# ARK.net
KiCad netlist of a schematic drawn in EAGLE
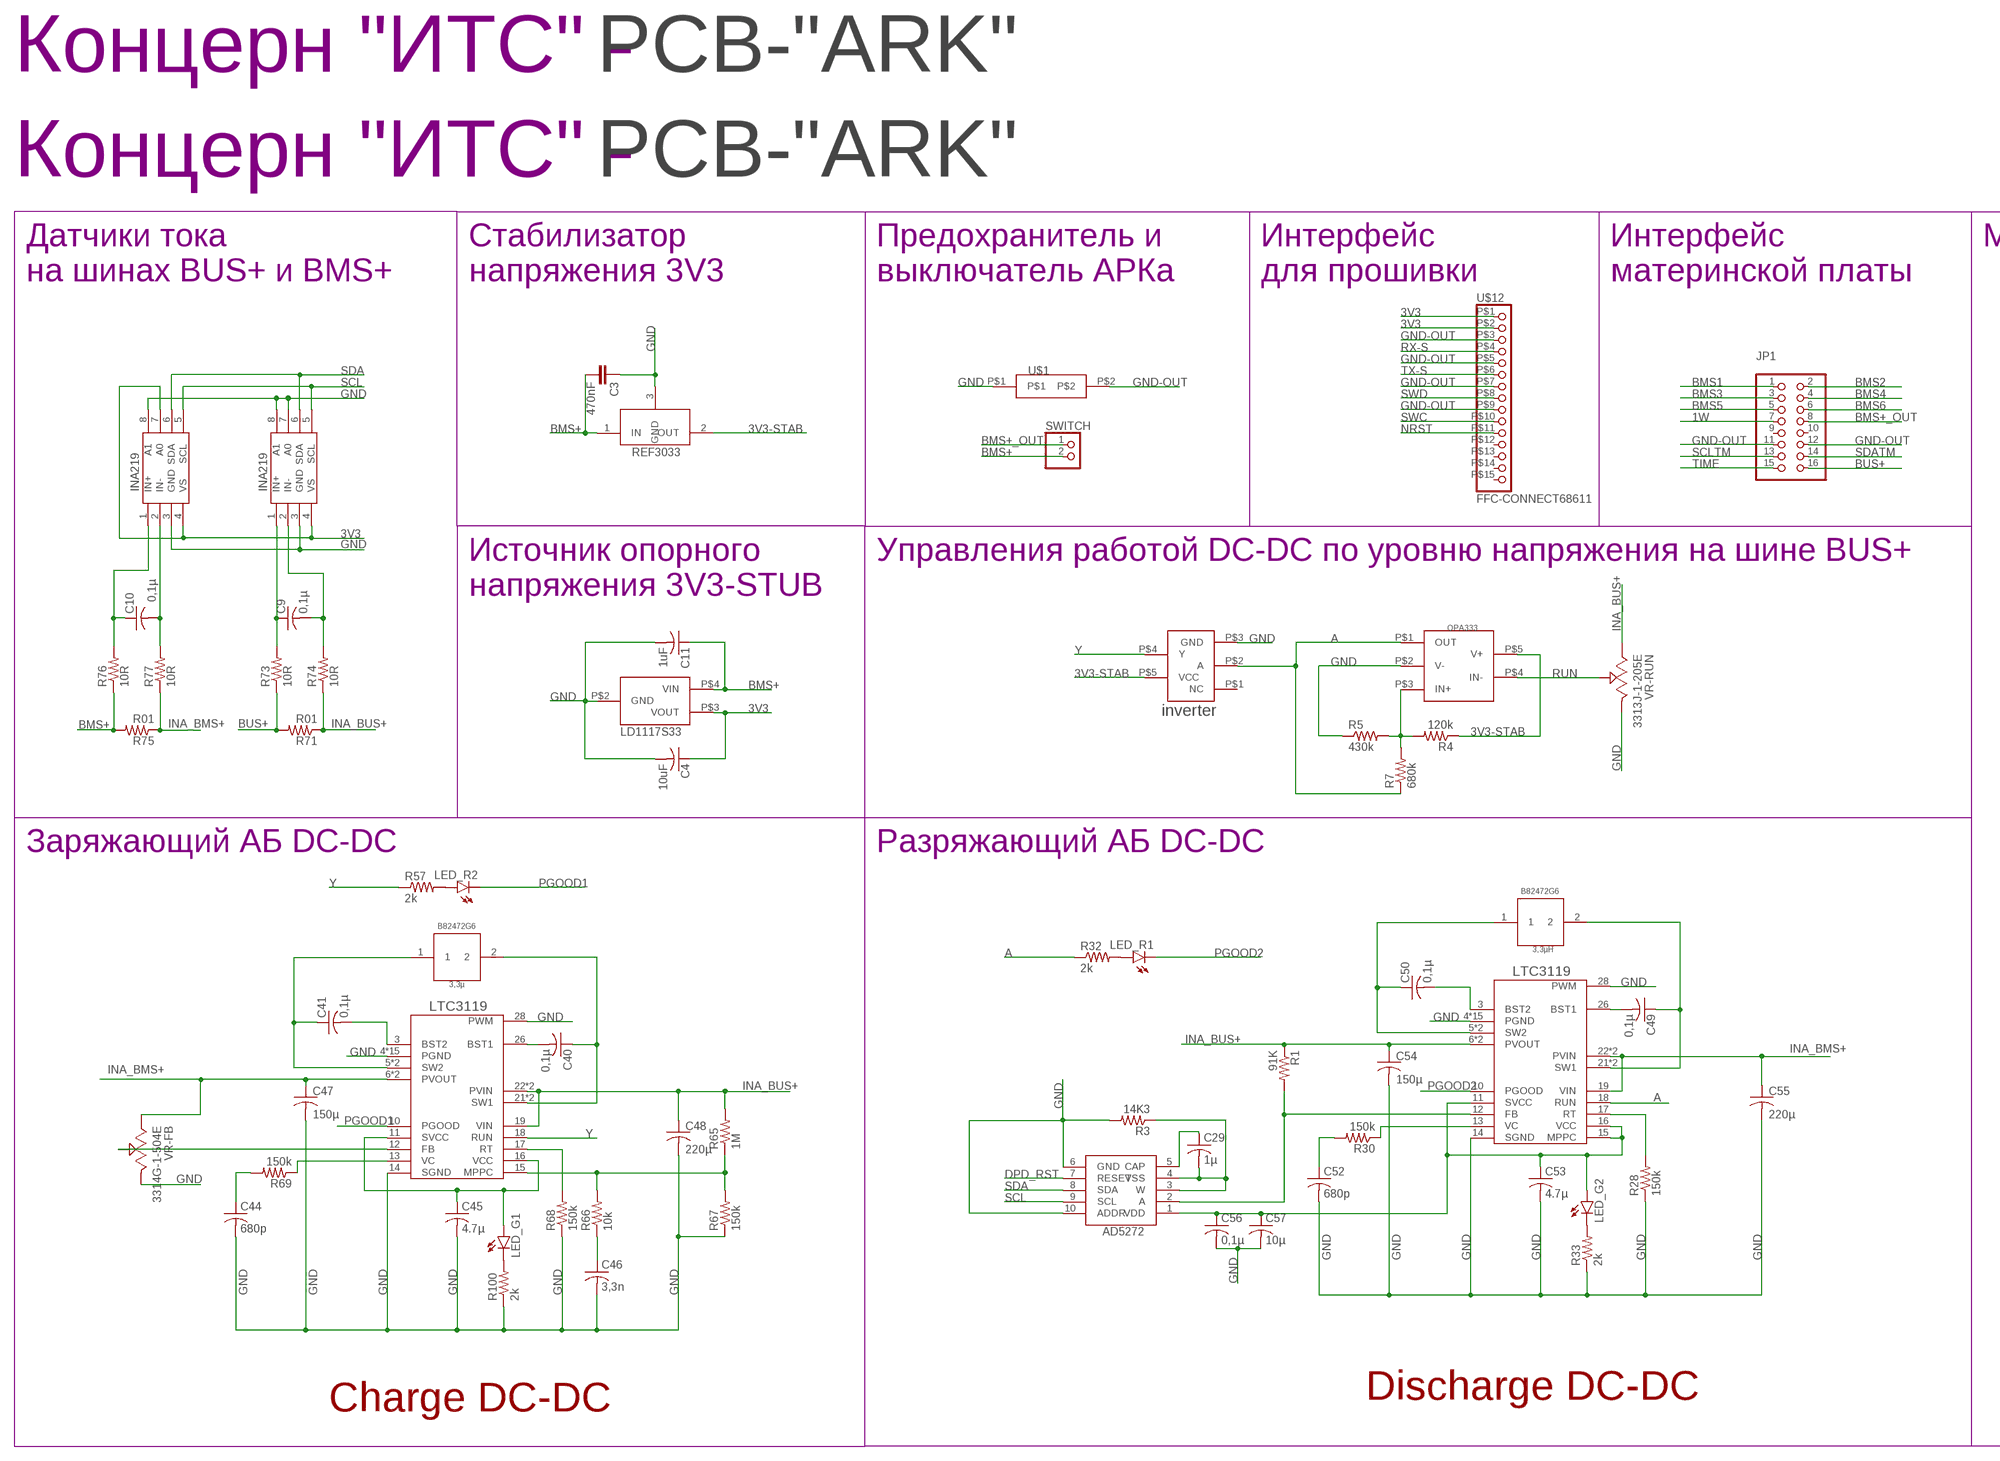
[diagram p0: schematic, sheet 1, part 1 of 2]
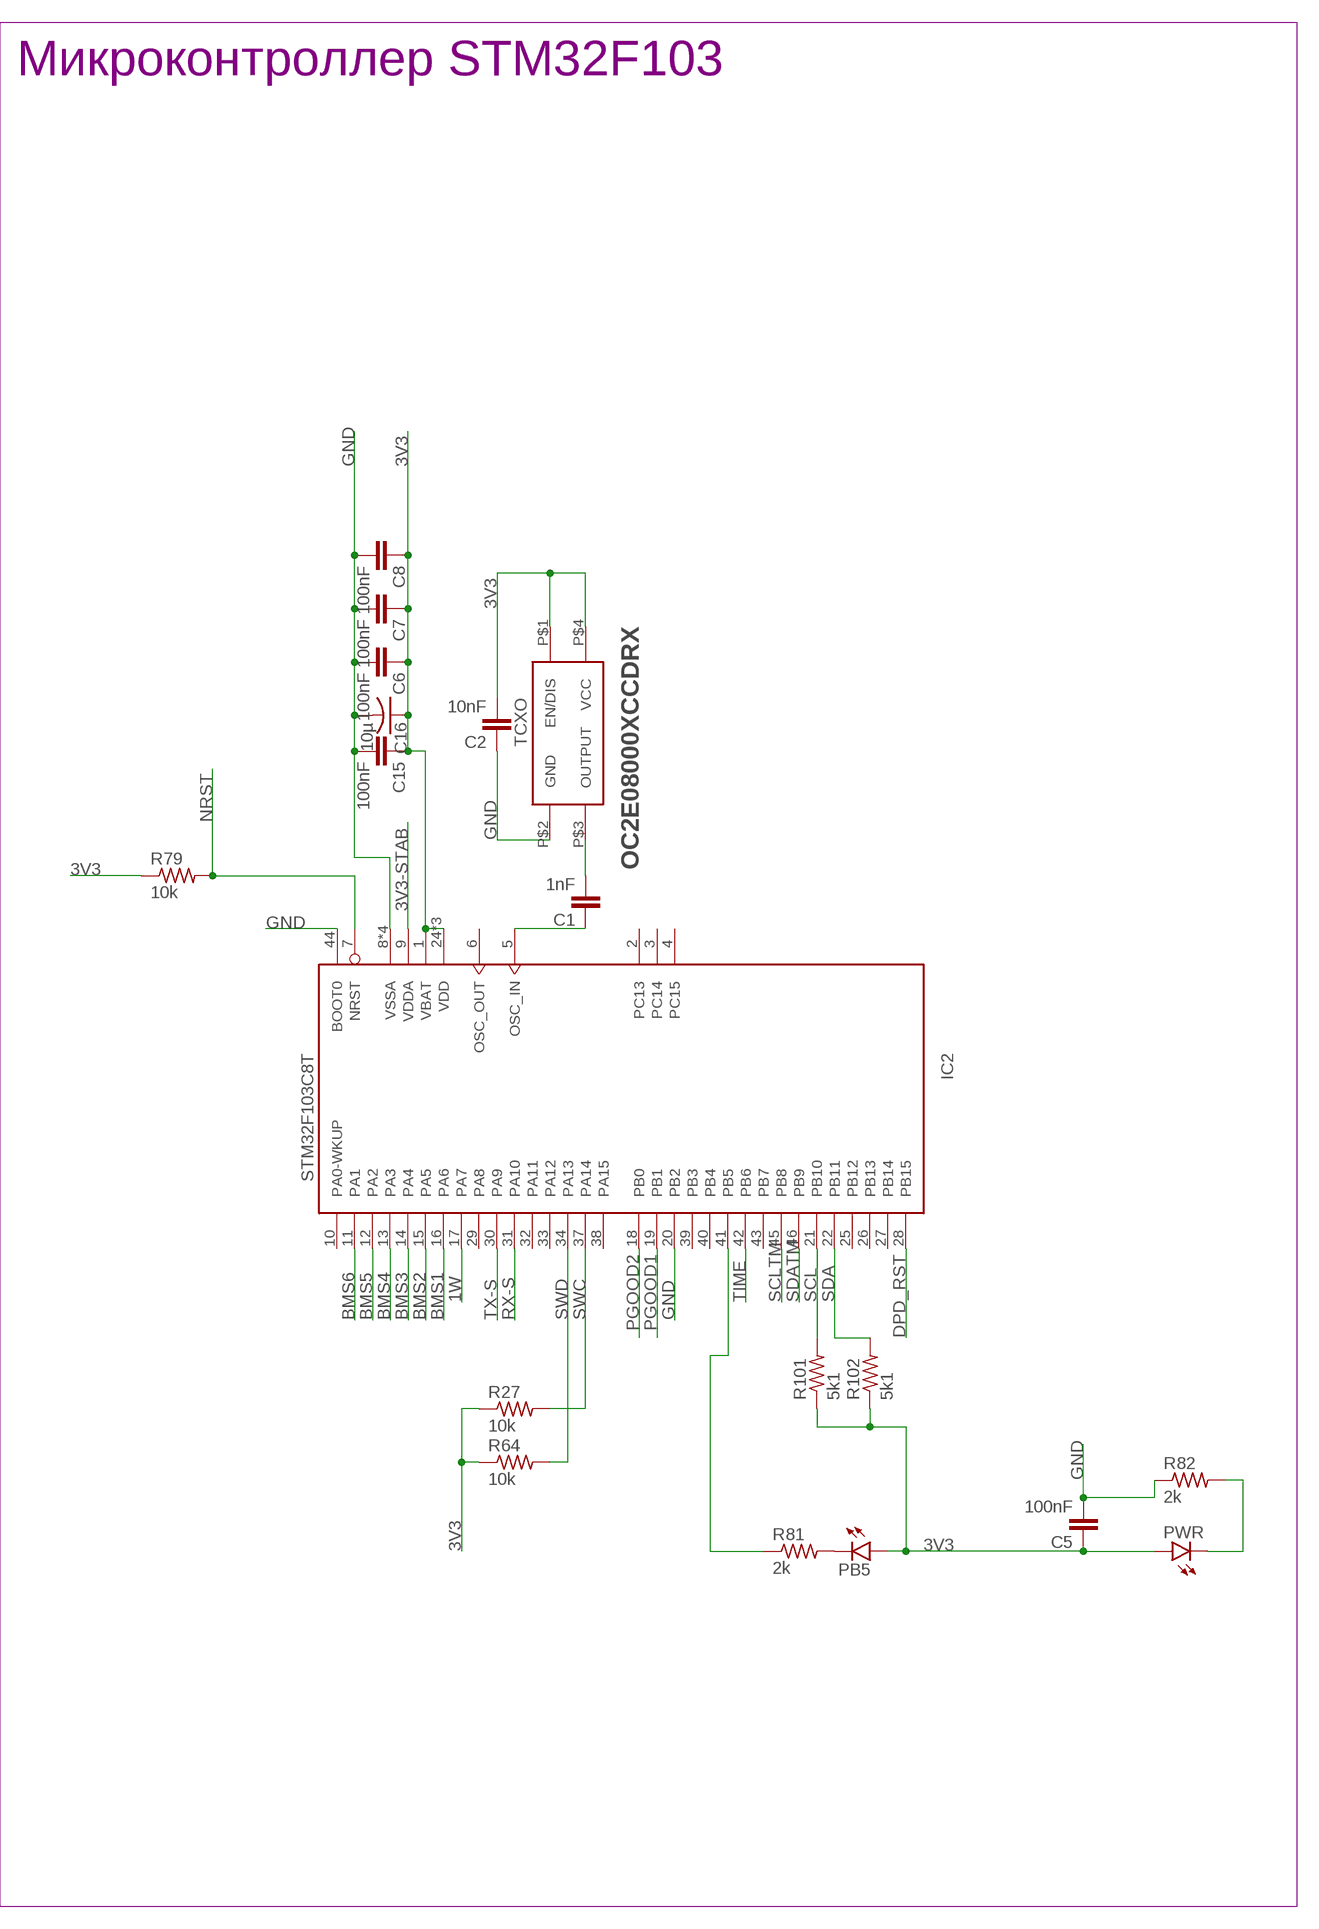
[diagram p1: schematic, sheet 1, part 2 of 2]

(export (version "E")
  (design (tool "Eeschema 10.0.6"))
  (components
    (comp (ref "3,3µH")
      (value "3,3µ")
      (footprint "eagle-import:B82472G6")
      (libsource (lib "eagle-import") (part "B82472G6"))
    )
    (comp (ref "3,3µH1")
      (value "3,3µH")
      (footprint "eagle-import:B82472G6")
      (libsource (lib "eagle-import") (part "B82472G6"))
    )
    (comp (ref "AD5272#2")
      (value "AD5272")
      (footprint "eagle-import:MSOP10")
      (libsource (lib "eagle-import") (part "AD5272"))
    )
    (comp (ref "C1")
      (value "1nF")
      (footprint "eagle-import:C0603")
      (libsource (lib "eagle-import") (part "C-EUC0603"))
    )
    (comp (ref "C2")
      (value "10nF")
      (footprint "eagle-import:C0603")
      (libsource (lib "eagle-import") (part "C-EUC0603"))
    )
    (comp (ref "C3")
      (value "470nF")
      (footprint "eagle-import:C0603")
      (libsource (lib "eagle-import") (part "C-EUC0603"))
    )
    (comp (ref "C4")
      (value "10uF")
      (footprint "eagle-import:ECAP-SMD-D4")
      (libsource (lib "eagle-import") (part "ECAP1UF"))
    )
    (comp (ref "C5")
      (value "100nF")
      (footprint "eagle-import:C0603")
      (libsource (lib "eagle-import") (part "C-EUC0603"))
    )
    (comp (ref "C6")
      (value "100nF")
      (footprint "eagle-import:C0603")
      (libsource (lib "eagle-import") (part "C-EUC0603"))
    )
    (comp (ref "C7")
      (value "100nF")
      (footprint "eagle-import:C0603")
      (libsource (lib "eagle-import") (part "C-EUC0603"))
    )
    (comp (ref "C8")
      (value "100nF")
      (footprint "eagle-import:C0603")
      (libsource (lib "eagle-import") (part "C-EUC0603"))
    )
    (comp (ref "C9")
      (value "0,1µ")
      (footprint "eagle-import:C0603")
      (libsource (lib "eagle-import") (part "C-USC0603"))
    )
    (comp (ref "C10")
      (value "0,1µ")
      (footprint "eagle-import:C0603")
      (libsource (lib "eagle-import") (part "C-USC0603"))
    )
    (comp (ref "C11")
      (value "1uF")
      (footprint "eagle-import:ECAP-SMD-D4")
      (libsource (lib "eagle-import") (part "ECAP1UF"))
    )
    (comp (ref "C15")
      (value "100nF")
      (footprint "eagle-import:C0603")
      (libsource (lib "eagle-import") (part "C-EUC0603"))
    )
    (comp (ref "C16")
      (value "10µ")
      (footprint "eagle-import:C1206")
      (libsource (lib "eagle-import") (part "C-USC1206"))
    )
    (comp (ref "C29")
      (value "1µ")
      (footprint "eagle-import:C0603")
      (libsource (lib "eagle-import") (part "C-USC0603"))
    )
    (comp (ref "C40")
      (value "0,1µ")
      (footprint "eagle-import:C0603")
      (libsource (lib "eagle-import") (part "C-USC0603"))
    )
    (comp (ref "C41")
      (value "0,1µ")
      (footprint "eagle-import:C0603")
      (libsource (lib "eagle-import") (part "C-USC0603"))
    )
    (comp (ref "C44")
      (value "680p")
      (footprint "eagle-import:C0603")
      (libsource (lib "eagle-import") (part "C-USC0603"))
    )
    (comp (ref "C45")
      (value "4.7µ")
      (footprint "eagle-import:C1206")
      (libsource (lib "eagle-import") (part "C-USC1206"))
    )
    (comp (ref "C46")
      (value "3,3n")
      (footprint "eagle-import:C0603")
      (libsource (lib "eagle-import") (part "C-USC0603"))
    )
    (comp (ref "C47")
      (value "150µ")
      (footprint "eagle-import:ECAP150-CMD")
      (libsource (lib "eagle-import") (part "ECAPECAP150"))
    )
    (comp (ref "C48")
      (value "220µ")
      (footprint "eagle-import:ECAP220-CMD")
      (libsource (lib "eagle-import") (part "ECAPECAP220"))
    )
    (comp (ref "C49")
      (value "0,1µ")
      (footprint "eagle-import:C0603")
      (libsource (lib "eagle-import") (part "C-USC0603"))
    )
    (comp (ref "C50")
      (value "0,1µ")
      (footprint "eagle-import:C0603")
      (libsource (lib "eagle-import") (part "C-USC0603"))
    )
    (comp (ref "C52")
      (value "680p")
      (footprint "eagle-import:C0603")
      (libsource (lib "eagle-import") (part "C-USC0603"))
    )
    (comp (ref "C53")
      (value "4.7µ")
      (footprint "eagle-import:C1206")
      (libsource (lib "eagle-import") (part "C-USC1206"))
    )
    (comp (ref "C54")
      (value "150µ")
      (footprint "eagle-import:ECAP150-CMD")
      (libsource (lib "eagle-import") (part "ECAPECAP150"))
    )
    (comp (ref "C55")
      (value "220µ")
      (footprint "eagle-import:ECAP220-CMD")
      (libsource (lib "eagle-import") (part "ECAPECAP220"))
    )
    (comp (ref "C56")
      (value "0,1µ")
      (footprint "eagle-import:C0603")
      (libsource (lib "eagle-import") (part "C-USC0603"))
    )
    (comp (ref "C57")
      (value "10µ")
      (footprint "eagle-import:C1206")
      (libsource (lib "eagle-import") (part "C-USC1206"))
    )
    (comp (ref "IC2")
      (value "STM32F103C8T")
      (footprint "eagle-import:LQFP48")
      (libsource (lib "eagle-import") (part "STM32F103CT8"))
    )
    (comp (ref "INA219#1")
      (value "INA219AID")
      (footprint "eagle-import:SOT23-8")
      (libsource (lib "eagle-import") (part "INA219AID"))
    )
    (comp (ref "INA219#2")
      (value "INA219AID")
      (footprint "eagle-import:SOT23-8")
      (libsource (lib "eagle-import") (part "INA219AID"))
    )
    (comp (ref "INVERT")
      (value "INVERTER.")
      (footprint "eagle-import:SC70")
      (libsource (lib "eagle-import") (part "INVERTER."))
    )
    (comp (ref "JP1")
      (value "PINHD-2X8")
      (footprint "eagle-import:2X08")
      (libsource (lib "eagle-import") (part "PINHD-2X8"))
    )
    (comp (ref "LD1117S33")
      (value "LD1117S33")
      (footprint "eagle-import:SOT223")
      (libsource (lib "eagle-import") (part "LD1117S33"))
    )
    (comp (ref "LED_G1")
      (value "LEDCHIPLED_0603")
      (footprint "eagle-import:CHIPLED_0603")
      (libsource (lib "eagle-import") (part "LEDCHIPLED_0603"))
    )
    (comp (ref "LED_G2")
      (value "LEDCHIPLED_0603")
      (footprint "eagle-import:CHIPLED_0603")
      (libsource (lib "eagle-import") (part "LEDCHIPLED_0603"))
    )
    (comp (ref "LED_R1")
      (value "LEDCHIPLED_0603")
      (footprint "eagle-import:CHIPLED_0603")
      (libsource (lib "eagle-import") (part "LEDCHIPLED_0603"))
    )
    (comp (ref "LED_R2")
      (value "LEDCHIPLED_0603")
      (footprint "eagle-import:CHIPLED_0603")
      (libsource (lib "eagle-import") (part "LEDCHIPLED_0603"))
    )
    (comp (ref "OPA")
      (value "OPA333")
      (footprint "eagle-import:SOT23-5")
      (libsource (lib "eagle-import") (part "OPA333"))
    )
    (comp (ref "PB5")
      (value "LEDCHIPLED_0603")
      (footprint "eagle-import:CHIPLED_0603")
      (libsource (lib "eagle-import") (part "LEDCHIPLED_0603"))
    )
    (comp (ref "PWR")
      (value "LEDCHIPLED_0603")
      (footprint "eagle-import:CHIPLED_0603")
      (libsource (lib "eagle-import") (part "LEDCHIPLED_0603"))
    )
    (comp (ref "R1")
      (value "91K")
      (footprint "eagle-import:R0603")
      (libsource (lib "eagle-import") (part "resistor_R-US_R0603"))
    )
    (comp (ref "R3")
      (value "14K3")
      (footprint "eagle-import:R0603")
      (libsource (lib "eagle-import") (part "resistor_R-US_R0603"))
    )
    (comp (ref "R4")
      (value "120k")
      (footprint "eagle-import:R0603")
      (libsource (lib "eagle-import") (part "resistor_R-US_R0603"))
    )
    (comp (ref "R5")
      (value "430k")
      (footprint "eagle-import:R0603")
      (libsource (lib "eagle-import") (part "resistor_R-US_R0603"))
    )
    (comp (ref "R7")
      (value "680k")
      (footprint "eagle-import:R0603")
      (libsource (lib "eagle-import") (part "resistor_R-US_R0603"))
    )
    (comp (ref "R27")
      (value "10k")
      (footprint "eagle-import:R0603")
      (libsource (lib "eagle-import") (part "resistor_R-US_R0603"))
    )
    (comp (ref "R28")
      (value "150k")
      (footprint "eagle-import:R0603")
      (libsource (lib "eagle-import") (part "resistor_R-US_R0603"))
    )
    (comp (ref "R30")
      (value "150k")
      (footprint "eagle-import:R0603")
      (libsource (lib "eagle-import") (part "resistor_R-US_R0603"))
    )
    (comp (ref "R32")
      (value "2k")
      (footprint "eagle-import:R0603")
      (libsource (lib "eagle-import") (part "resistor_R-US_R0603"))
    )
    (comp (ref "R33")
      (value "2k")
      (footprint "eagle-import:R0603")
      (libsource (lib "eagle-import") (part "resistor_R-US_R0603"))
    )
    (comp (ref "R57")
      (value "2k")
      (footprint "eagle-import:R0603")
      (libsource (lib "eagle-import") (part "resistor_R-US_R0603"))
    )
    (comp (ref "R64")
      (value "10k")
      (footprint "eagle-import:R0603")
      (libsource (lib "eagle-import") (part "resistor_R-US_R0603"))
    )
    (comp (ref "R65")
      (value "1M")
      (footprint "eagle-import:R0603")
      (libsource (lib "eagle-import") (part "resistor_R-US_R0603"))
    )
    (comp (ref "R66")
      (value "10k")
      (footprint "eagle-import:R0603")
      (libsource (lib "eagle-import") (part "resistor_R-US_R0603"))
    )
    (comp (ref "R67")
      (value "150k")
      (footprint "eagle-import:R0603")
      (libsource (lib "eagle-import") (part "resistor_R-US_R0603"))
    )
    (comp (ref "R68")
      (value "150k")
      (footprint "eagle-import:R0603")
      (libsource (lib "eagle-import") (part "resistor_R-US_R0603"))
    )
    (comp (ref "R69")
      (value "150k")
      (footprint "eagle-import:R0603")
      (libsource (lib "eagle-import") (part "resistor_R-US_R0603"))
    )
    (comp (ref "R71")
      (value "R01")
      (footprint "eagle-import:R2512")
      (libsource (lib "eagle-import") (part "R-US_R2512"))
    )
    (comp (ref "R73")
      (value "10R")
      (footprint "eagle-import:R0603")
      (libsource (lib "eagle-import") (part "resistor_R-US_R0603"))
    )
    (comp (ref "R74")
      (value "10R")
      (footprint "eagle-import:R0603")
      (libsource (lib "eagle-import") (part "resistor_R-US_R0603"))
    )
    (comp (ref "R75")
      (value "R01")
      (footprint "eagle-import:R2512")
      (libsource (lib "eagle-import") (part "R-US_R2512"))
    )
    (comp (ref "R76")
      (value "10R")
      (footprint "eagle-import:R0603")
      (libsource (lib "eagle-import") (part "resistor_R-US_R0603"))
    )
    (comp (ref "R77")
      (value "10R")
      (footprint "eagle-import:R0603")
      (libsource (lib "eagle-import") (part "resistor_R-US_R0603"))
    )
    (comp (ref "R79")
      (value "10k")
      (footprint "eagle-import:R0603")
      (libsource (lib "eagle-import") (part "resistor_R-US_R0603"))
    )
    (comp (ref "R81")
      (value "2k")
      (footprint "eagle-import:R0603")
      (libsource (lib "eagle-import") (part "resistor_R-US_R0603"))
    )
    (comp (ref "R82")
      (value "2k")
      (footprint "eagle-import:R0603")
      (libsource (lib "eagle-import") (part "resistor_R-US_R0603"))
    )
    (comp (ref "R100")
      (value "2k")
      (footprint "eagle-import:R0603")
      (libsource (lib "eagle-import") (part "resistor_R-US_R0603"))
    )
    (comp (ref "R101")
      (value "5k1")
      (footprint "eagle-import:R0603")
      (libsource (lib "eagle-import") (part "resistor_R-US_R0603"))
    )
    (comp (ref "R102")
      (value "5k1")
      (footprint "eagle-import:R0603")
      (libsource (lib "eagle-import") (part "resistor_R-US_R0603"))
    )
    (comp (ref "REF3033")
      (value "REF3033")
      (footprint "eagle-import:SOT23-3")
      (libsource (lib "eagle-import") (part "REF3033"))
    )
    (comp (ref "SWITCH")
      (value "PINHD-1X2")
      (footprint "eagle-import:1X02")
      (libsource (lib "eagle-import") (part "PINHD-1X2"))
    )
    (comp (ref "TCXO")
      (value "OC2E08000XCCDRX")
      (footprint "eagle-import:OC2E08000XCCDRX")
      (libsource (lib "eagle-import") (part "OC2E08000XCCDRX"))
    )
    (comp (ref "U$1")
      (value "MF-R400")
      (footprint "eagle-import:MF-R400")
      (libsource (lib "eagle-import") (part "MF-R400"))
    )
    (comp (ref "U$3")
      (value "PCB-\"ARK\"")
      (footprint "eagle-import:ITS-LOGO")
      (libsource (lib "eagle-import") (part "ITS-LOGOPCB-{dblquote}{dblquote}"))
    )
    (comp (ref "U$4")
      (value "PCB-\"ARK\"")
      (footprint "eagle-import:ITS-LOGO")
      (libsource (lib "eagle-import") (part "ITS-LOGOPCB-{dblquote}{dblquote}"))
    )
    (comp (ref "U$12")
      (value "FFC-CONNECT68611")
      (footprint "eagle-import:68611")
      (libsource (lib "eagle-import") (part "FFC-CONNECT68611"))
    )
    (comp (ref "U$23")
      (value "LTC31191")
      (footprint "eagle-import:LTC3119+VIA")
      (libsource (lib "eagle-import") (part "LTC31191"))
    )
    (comp (ref "U$59")
      (value "LTC31191")
      (footprint "eagle-import:LTC3119+VIA")
      (libsource (lib "eagle-import") (part "LTC31191"))
    )
    (comp (ref "VR-FB")
      (value "3314G-1-504E")
      (footprint "eagle-import:TRIM_3314G-1-504E")
      (libsource (lib "eagle-import") (part "3314G-1-504E"))
    )
    (comp (ref "VR-RUN")
      (value "3313J-1-205E")
      (footprint "eagle-import:TRIM_3313J-1-205E")
      (fields (field (name "MF") "Bourns") (field (name "MP") "3313J-1-104E"))
      (libsource (lib "eagle-import") (part "3313J-1-205E"))
    )
  )
  (nets
    (net (code "1") (name "/1W") (class "Default")
      (node (ref "IC2") (pin "17") (pinfunction "PA7_17") (pintype "bidirectional"))
      (node (ref "JP1") (pin "7") (pinfunction "7_7") (pintype "passive"))
    )
    (net (code "2") (name "/3V3") (class "Default")
      (node (ref "C15") (pin "1") (pinfunction "1_1") (pintype "passive"))
      (node (ref "C16") (pin "1") (pinfunction "1_1") (pintype "passive"))
      (node (ref "C2") (pin "2") (pinfunction "2_2") (pintype "passive"))
      (node (ref "C4") (pin "P+") (pinfunction "1_P+") (pintype "passive"))
      (node (ref "C5") (pin "1") (pinfunction "1_1") (pintype "passive"))
      (node (ref "C6") (pin "1") (pinfunction "1_1") (pintype "passive"))
      (node (ref "C7") (pin "1") (pinfunction "1_1") (pintype "passive"))
      (node (ref "C8") (pin "1") (pinfunction "1_1") (pintype "passive"))
      (node (ref "IC2") (pin "1") (pinfunction "VBAT_1") (pintype "power_in"))
      (node (ref "IC2") (pin "24") (pinfunction "VDD_24") (pintype "bidirectional"))
      (node (ref "IC2") (pin "36") (pinfunction "VDD_36") (pintype "bidirectional"))
      (node (ref "IC2") (pin "48") (pinfunction "VDD_48") (pintype "bidirectional"))
      (node (ref "INA219#1") (pin "4") (pinfunction "VS_4") (pintype "bidirectional"))
      (node (ref "INA219#2") (pin "4") (pinfunction "VS_4") (pintype "bidirectional"))
      (node (ref "INA219#2") (pin "7") (pinfunction "A0_7") (pintype "bidirectional"))
      (node (ref "LD1117S33") (pin "P$3") (pinfunction "VOUT_P$3") (pintype "bidirectional"))
      (node (ref "PB5") (pin "A") (pinfunction "A_A") (pintype "passive"))
      (node (ref "PWR") (pin "A") (pinfunction "A_A") (pintype "passive"))
      (node (ref "R101") (pin "1") (pinfunction "1_1") (pintype "passive"))
      (node (ref "R102") (pin "1") (pinfunction "1_1") (pintype "passive"))
      (node (ref "R27") (pin "1") (pinfunction "1_1") (pintype "passive"))
      (node (ref "R64") (pin "1") (pinfunction "1_1") (pintype "passive"))
      (node (ref "R79") (pin "1") (pinfunction "1_1") (pintype "passive"))
      (node (ref "TCXO") (pin "P$1") (pinfunction "EN/DIS_P$1") (pintype "bidirectional"))
      (node (ref "TCXO") (pin "P$4") (pinfunction "VCC_P$4") (pintype "bidirectional"))
      (node (ref "U$12") (pin "P$1") (pinfunction "1_P$1") (pintype "passive"))
      (node (ref "U$12") (pin "P$2") (pinfunction "2_P$2") (pintype "passive"))
    )
    (net (code "3") (name "/3V3-STAB") (class "Default")
      (node (ref "IC2") (pin "9") (pinfunction "VDDA_9") (pintype "power_in"))
      (node (ref "INVERT") (pin "P$5") (pinfunction "VCC_P$5") (pintype "bidirectional"))
      (node (ref "OPA") (pin "P$5") (pinfunction "V+_P$5") (pintype "bidirectional"))
      (node (ref "R4") (pin "1") (pinfunction "1_1") (pintype "passive"))
      (node (ref "REF3033") (pin "2") (pinfunction "OUT_2") (pintype "output"))
    )
    (net (code "4") (name "/A") (class "Default")
      (node (ref "INVERT") (pin "P$2") (pinfunction "A_P$2") (pintype "bidirectional"))
      (node (ref "OPA") (pin "P$1") (pinfunction "OUT_P$1") (pintype "bidirectional"))
      (node (ref "R32") (pin "1") (pinfunction "1_1") (pintype "passive"))
      (node (ref "R7") (pin "1") (pinfunction "1_1") (pintype "passive"))
      (node (ref "U$23") (pin "18") (pinfunction "RUN_18") (pintype "bidirectional"))
    )
    (net (code "5") (name "/BMS+") (class "Default")
      (node (ref "C11") (pin "P+") (pinfunction "1_P+") (pintype "passive"))
      (node (ref "C3") (pin "2") (pinfunction "2_2") (pintype "passive"))
      (node (ref "LD1117S33") (pin "P$4") (pinfunction "VIN_P$4") (pintype "bidirectional"))
      (node (ref "R75") (pin "2") (pinfunction "2_2") (pintype "passive"))
      (node (ref "R76") (pin "1") (pinfunction "1_1") (pintype "passive"))
      (node (ref "REF3033") (pin "1") (pinfunction "IN_1") (pintype "input"))
      (node (ref "SWITCH") (pin "2") (pinfunction "2_2") (pintype "passive"))
    )
    (net (code "6") (name "/BMS+_OUT") (class "Default")
      (node (ref "JP1") (pin "8") (pinfunction "8_8") (pintype "passive"))
      (node (ref "SWITCH") (pin "1") (pinfunction "1_1") (pintype "passive"))
    )
    (net (code "7") (name "/BMS1") (class "Default")
      (node (ref "IC2") (pin "16") (pinfunction "PA6_16") (pintype "bidirectional"))
      (node (ref "JP1") (pin "1") (pinfunction "1_1") (pintype "passive"))
    )
    (net (code "8") (name "/BMS2") (class "Default")
      (node (ref "IC2") (pin "15") (pinfunction "PA5_15") (pintype "bidirectional"))
      (node (ref "JP1") (pin "2") (pinfunction "2_2") (pintype "passive"))
    )
    (net (code "9") (name "/BMS3") (class "Default")
      (node (ref "IC2") (pin "14") (pinfunction "PA4_14") (pintype "bidirectional"))
      (node (ref "JP1") (pin "3") (pinfunction "3_3") (pintype "passive"))
    )
    (net (code "10") (name "/BMS4") (class "Default")
      (node (ref "IC2") (pin "13") (pinfunction "PA3_13") (pintype "bidirectional"))
      (node (ref "JP1") (pin "4") (pinfunction "4_4") (pintype "passive"))
    )
    (net (code "11") (name "/BMS5") (class "Default")
      (node (ref "IC2") (pin "12") (pinfunction "PA2_12") (pintype "bidirectional"))
      (node (ref "JP1") (pin "5") (pinfunction "5_5") (pintype "passive"))
    )
    (net (code "12") (name "/BMS6") (class "Default")
      (node (ref "IC2") (pin "11") (pinfunction "PA1_11") (pintype "bidirectional"))
      (node (ref "JP1") (pin "6") (pinfunction "6_6") (pintype "passive"))
    )
    (net (code "13") (name "/BUS+") (class "Default")
      (node (ref "JP1") (pin "16") (pinfunction "16_16") (pintype "passive"))
      (node (ref "R71") (pin "2") (pinfunction "2_2") (pintype "passive"))
      (node (ref "R73") (pin "1") (pinfunction "1_1") (pintype "passive"))
    )
    (net (code "14") (name "/DPD_RST") (class "Default")
      (node (ref "AD5272#2") (pin "7") (pinfunction "RESET_7") (pintype "bidirectional"))
      (node (ref "IC2") (pin "28") (pinfunction "PB15_28") (pintype "bidirectional"))
    )
    (net (code "15") (name "/GND") (class "Default")
      (node (ref "AD5272#2") (pin "10") (pinfunction "ADDR_10") (pintype "bidirectional"))
      (node (ref "AD5272#2") (pin "6") (pinfunction "GND_6") (pintype "bidirectional"))
      (node (ref "C11") (pin "P-") (pinfunction "2_P-") (pintype "passive"))
      (node (ref "C15") (pin "2") (pinfunction "2_2") (pintype "passive"))
      (node (ref "C16") (pin "2") (pinfunction "2_2") (pintype "passive"))
      (node (ref "C2") (pin "1") (pinfunction "1_1") (pintype "passive"))
      (node (ref "C3") (pin "1") (pinfunction "1_1") (pintype "passive"))
      (node (ref "C4") (pin "P-") (pinfunction "2_P-") (pintype "passive"))
      (node (ref "C44") (pin "2") (pinfunction "2_2") (pintype "passive"))
      (node (ref "C45") (pin "2") (pinfunction "2_2") (pintype "passive"))
      (node (ref "C46") (pin "2") (pinfunction "2_2") (pintype "passive"))
      (node (ref "C47") (pin "P$2") (pinfunction "2_P$2") (pintype "passive"))
      (node (ref "C48") (pin "P$2") (pinfunction "2_P$2") (pintype "passive"))
      (node (ref "C5") (pin "2") (pinfunction "2_2") (pintype "passive"))
      (node (ref "C52") (pin "2") (pinfunction "2_2") (pintype "passive"))
      (node (ref "C53") (pin "2") (pinfunction "2_2") (pintype "passive"))
      (node (ref "C54") (pin "P$2") (pinfunction "2_P$2") (pintype "passive"))
      (node (ref "C55") (pin "P$2") (pinfunction "2_P$2") (pintype "passive"))
      (node (ref "C56") (pin "2") (pinfunction "2_2") (pintype "passive"))
      (node (ref "C57") (pin "2") (pinfunction "2_2") (pintype "passive"))
      (node (ref "C6") (pin "2") (pinfunction "2_2") (pintype "passive"))
      (node (ref "C7") (pin "2") (pinfunction "2_2") (pintype "passive"))
      (node (ref "C8") (pin "2") (pinfunction "2_2") (pintype "passive"))
      (node (ref "IC2") (pin "20") (pinfunction "PB2_20") (pintype "bidirectional"))
      (node (ref "IC2") (pin "23") (pinfunction "VSSA_23") (pintype "power_in"))
      (node (ref "IC2") (pin "35") (pinfunction "VSSA_35") (pintype "power_in"))
      (node (ref "IC2") (pin "44") (pinfunction "BOOT0_44") (pintype "input"))
      (node (ref "IC2") (pin "47") (pinfunction "VSSA_47") (pintype "power_in"))
      (node (ref "IC2") (pin "8") (pinfunction "VSSA_8") (pintype "power_in"))
      (node (ref "INA219#1") (pin "3") (pinfunction "GND_3") (pintype "bidirectional"))
      (node (ref "INA219#1") (pin "7") (pinfunction "A0_7") (pintype "bidirectional"))
      (node (ref "INA219#1") (pin "8") (pinfunction "A1_8") (pintype "bidirectional"))
      (node (ref "INA219#2") (pin "3") (pinfunction "GND_3") (pintype "bidirectional"))
      (node (ref "INA219#2") (pin "8") (pinfunction "A1_8") (pintype "bidirectional"))
      (node (ref "INVERT") (pin "P$3") (pinfunction "GND_P$3") (pintype "bidirectional"))
      (node (ref "LD1117S33") (pin "P$2") (pinfunction "GND_P$2") (pintype "bidirectional"))
      (node (ref "OPA") (pin "P$2") (pinfunction "V-_P$2") (pintype "bidirectional"))
      (node (ref "R100") (pin "1") (pinfunction "1_1") (pintype "passive"))
      (node (ref "R28") (pin "1") (pinfunction "1_1") (pintype "passive"))
      (node (ref "R3") (pin "2") (pinfunction "2_2") (pintype "passive"))
      (node (ref "R33") (pin "1") (pinfunction "1_1") (pintype "passive"))
      (node (ref "R5") (pin "1") (pinfunction "1_1") (pintype "passive"))
      (node (ref "R67") (pin "1") (pinfunction "1_1") (pintype "passive"))
      (node (ref "R68") (pin "1") (pinfunction "1_1") (pintype "passive"))
      (node (ref "R82") (pin "1") (pinfunction "1_1") (pintype "passive"))
      (node (ref "REF3033") (pin "3") (pinfunction "GND_3") (pintype "power_in"))
      (node (ref "TCXO") (pin "P$2") (pinfunction "GND_P$2") (pintype "bidirectional"))
      (node (ref "U$1") (pin "P$1") (pinfunction "P$1_P$1") (pintype "bidirectional"))
      (node (ref "U$23") (pin "14") (pinfunction "SGND_14") (pintype "bidirectional"))
      (node (ref "U$23") (pin "20") (pinfunction "PGND_20") (pintype "bidirectional"))
      (node (ref "U$23") (pin "25") (pinfunction "PGND_25") (pintype "bidirectional"))
      (node (ref "U$23") (pin "28") (pinfunction "PWM_28") (pintype "bidirectional"))
      (node (ref "U$23") (pin "29") (pinfunction "PGND_29") (pintype "bidirectional"))
      (node (ref "U$23") (pin "4") (pinfunction "PGND_4") (pintype "bidirectional"))
      (node (ref "U$23") (pin "9") (pinfunction "PGND_9") (pintype "bidirectional"))
      (node (ref "U$23") (pin "P$1") (pinfunction "PGND_P$1") (pintype "bidirectional"))
      (node (ref "U$23") (pin "P$10") (pinfunction "PGND_P$10") (pintype "bidirectional"))
      (node (ref "U$23") (pin "P$2") (pinfunction "PGND_P$2") (pintype "bidirectional"))
      (node (ref "U$23") (pin "P$3") (pinfunction "PGND_P$3") (pintype "bidirectional"))
      (node (ref "U$23") (pin "P$4") (pinfunction "PGND_P$4") (pintype "bidirectional"))
      (node (ref "U$23") (pin "P$5") (pinfunction "PGND_P$5") (pintype "bidirectional"))
      (node (ref "U$23") (pin "P$6") (pinfunction "PGND_P$6") (pintype "bidirectional"))
      (node (ref "U$23") (pin "P$7") (pinfunction "PGND_P$7") (pintype "bidirectional"))
      (node (ref "U$23") (pin "P$8") (pinfunction "PGND_P$8") (pintype "bidirectional"))
      (node (ref "U$23") (pin "P$9") (pinfunction "PGND_P$9") (pintype "bidirectional"))
      (node (ref "U$59") (pin "14") (pinfunction "SGND_14") (pintype "bidirectional"))
      (node (ref "U$59") (pin "20") (pinfunction "PGND_20") (pintype "bidirectional"))
      (node (ref "U$59") (pin "25") (pinfunction "PGND_25") (pintype "bidirectional"))
      (node (ref "U$59") (pin "28") (pinfunction "PWM_28") (pintype "bidirectional"))
      (node (ref "U$59") (pin "29") (pinfunction "PGND_29") (pintype "bidirectional"))
      (node (ref "U$59") (pin "4") (pinfunction "PGND_4") (pintype "bidirectional"))
      (node (ref "U$59") (pin "9") (pinfunction "PGND_9") (pintype "bidirectional"))
      (node (ref "U$59") (pin "P$1") (pinfunction "PGND_P$1") (pintype "bidirectional"))
      (node (ref "U$59") (pin "P$10") (pinfunction "PGND_P$10") (pintype "bidirectional"))
      (node (ref "U$59") (pin "P$2") (pinfunction "PGND_P$2") (pintype "bidirectional"))
      (node (ref "U$59") (pin "P$3") (pinfunction "PGND_P$3") (pintype "bidirectional"))
      (node (ref "U$59") (pin "P$4") (pinfunction "PGND_P$4") (pintype "bidirectional"))
      (node (ref "U$59") (pin "P$5") (pinfunction "PGND_P$5") (pintype "bidirectional"))
      (node (ref "U$59") (pin "P$6") (pinfunction "PGND_P$6") (pintype "bidirectional"))
      (node (ref "U$59") (pin "P$7") (pinfunction "PGND_P$7") (pintype "bidirectional"))
      (node (ref "U$59") (pin "P$8") (pinfunction "PGND_P$8") (pintype "bidirectional"))
      (node (ref "U$59") (pin "P$9") (pinfunction "PGND_P$9") (pintype "bidirectional"))
      (node (ref "VR-FB") (pin "3") (pinfunction "CW_3") (pintype "passive"))
      (node (ref "VR-RUN") (pin "3") (pinfunction "CW_3") (pintype "passive"))
    )
    (net (code "16") (name "/GND-OUT") (class "Default")
      (node (ref "JP1") (pin "11") (pinfunction "11_11") (pintype "passive"))
      (node (ref "JP1") (pin "12") (pinfunction "12_12") (pintype "passive"))
      (node (ref "U$1") (pin "P$2") (pinfunction "P$2_P$2") (pintype "bidirectional"))
      (node (ref "U$12") (pin "P$3") (pinfunction "3_P$3") (pintype "passive"))
      (node (ref "U$12") (pin "P$5") (pinfunction "5_P$5") (pintype "passive"))
      (node (ref "U$12") (pin "P$7") (pinfunction "7_P$7") (pintype "passive"))
      (node (ref "U$12") (pin "P$9") (pinfunction "9_P$9") (pintype "passive"))
    )
    (net (code "17") (name "/INA_BMS+") (class "Default")
      (node (ref "C47") (pin "P$1") (pinfunction "1_P$1") (pintype "passive"))
      (node (ref "C55") (pin "P$1") (pinfunction "1_P$1") (pintype "passive"))
      (node (ref "R75") (pin "1") (pinfunction "1_1") (pintype "passive"))
      (node (ref "R77") (pin "1") (pinfunction "1_1") (pintype "passive"))
      (node (ref "U$23") (pin "19") (pinfunction "VIN_19") (pintype "bidirectional"))
      (node (ref "U$23") (pin "22") (pinfunction "PVIN_22") (pintype "bidirectional"))
      (node (ref "U$23") (pin "23") (pinfunction "PVIN_23") (pintype "bidirectional"))
      (node (ref "U$59") (pin "6") (pinfunction "PVOUT_6") (pintype "bidirectional"))
      (node (ref "U$59") (pin "7") (pinfunction "PVOUT_7") (pintype "bidirectional"))
      (node (ref "VR-FB") (pin "1") (pinfunction "CCW_1") (pintype "passive"))
    )
    (net (code "18") (name "/INA_BUS+") (class "Default")
      (node (ref "C48") (pin "P$1") (pinfunction "1_P$1") (pintype "passive"))
      (node (ref "C54") (pin "P$1") (pinfunction "1_P$1") (pintype "passive"))
      (node (ref "R1") (pin "1") (pinfunction "1_1") (pintype "passive"))
      (node (ref "R65") (pin "2") (pinfunction "2_2") (pintype "passive"))
      (node (ref "R71") (pin "1") (pinfunction "1_1") (pintype "passive"))
      (node (ref "R74") (pin "1") (pinfunction "1_1") (pintype "passive"))
      (node (ref "U$23") (pin "6") (pinfunction "PVOUT_6") (pintype "bidirectional"))
      (node (ref "U$23") (pin "7") (pinfunction "PVOUT_7") (pintype "bidirectional"))
      (node (ref "U$59") (pin "19") (pinfunction "VIN_19") (pintype "bidirectional"))
      (node (ref "U$59") (pin "22") (pinfunction "PVIN_22") (pintype "bidirectional"))
      (node (ref "U$59") (pin "23") (pinfunction "PVIN_23") (pintype "bidirectional"))
      (node (ref "VR-RUN") (pin "1") (pinfunction "CCW_1") (pintype "passive"))
    )
    (net (code "19") (name "/NRST") (class "Default")
      (node (ref "IC2") (pin "7") (pinfunction "NRST_7") (pintype "bidirectional"))
      (node (ref "R79") (pin "2") (pinfunction "2_2") (pintype "passive"))
      (node (ref "U$12") (pin "P$11") (pinfunction "11_P$11") (pintype "passive"))
    )
    (net (code "20") (name "/PGOOD1") (class "Default")
      (node (ref "IC2") (pin "19") (pinfunction "PB1_19") (pintype "bidirectional"))
      (node (ref "LED_R2") (pin "C") (pinfunction "C_C") (pintype "passive"))
      (node (ref "U$59") (pin "10") (pinfunction "PGOOD_10") (pintype "bidirectional"))
    )
    (net (code "21") (name "/PGOOD2") (class "Default")
      (node (ref "IC2") (pin "18") (pinfunction "PB0_18") (pintype "bidirectional"))
      (node (ref "LED_R1") (pin "C") (pinfunction "C_C") (pintype "passive"))
      (node (ref "U$23") (pin "10") (pinfunction "PGOOD_10") (pintype "bidirectional"))
    )
    (net (code "22") (name "/RUN") (class "Default")
      (node (ref "OPA") (pin "P$4") (pinfunction "IN-_P$4") (pintype "bidirectional"))
      (node (ref "VR-RUN") (pin "2") (pinfunction "WIPER_2") (pintype "passive"))
    )
    (net (code "23") (name "/RX-S") (class "Default")
      (node (ref "IC2") (pin "31") (pinfunction "PA10_31") (pintype "bidirectional"))
      (node (ref "U$12") (pin "P$4") (pinfunction "4_P$4") (pintype "passive"))
    )
    (net (code "24") (name "/SCL") (class "Default")
      (node (ref "AD5272#2") (pin "9") (pinfunction "SCL_9") (pintype "bidirectional"))
      (node (ref "IC2") (pin "21") (pinfunction "PB10_21") (pintype "bidirectional"))
      (node (ref "INA219#1") (pin "5") (pinfunction "SCL_5") (pintype "bidirectional"))
      (node (ref "INA219#2") (pin "5") (pinfunction "SCL_5") (pintype "bidirectional"))
      (node (ref "R101") (pin "2") (pinfunction "2_2") (pintype "passive"))
    )
    (net (code "25") (name "/SCLTM") (class "Default")
      (node (ref "IC2") (pin "45") (pinfunction "PB8_45") (pintype "bidirectional"))
      (node (ref "JP1") (pin "13") (pinfunction "13_13") (pintype "passive"))
    )
    (net (code "26") (name "/SDA") (class "Default")
      (node (ref "AD5272#2") (pin "8") (pinfunction "SDA_8") (pintype "bidirectional"))
      (node (ref "IC2") (pin "22") (pinfunction "PB11_22") (pintype "bidirectional"))
      (node (ref "INA219#1") (pin "6") (pinfunction "SDA_6") (pintype "bidirectional"))
      (node (ref "INA219#2") (pin "6") (pinfunction "SDA_6") (pintype "bidirectional"))
      (node (ref "R102") (pin "2") (pinfunction "2_2") (pintype "passive"))
    )
    (net (code "27") (name "/SDATM") (class "Default")
      (node (ref "IC2") (pin "46") (pinfunction "PB9_46") (pintype "bidirectional"))
      (node (ref "JP1") (pin "14") (pinfunction "14_14") (pintype "passive"))
    )
    (net (code "28") (name "/SWC") (class "Default")
      (node (ref "IC2") (pin "37") (pinfunction "PA14_37") (pintype "bidirectional"))
      (node (ref "R27") (pin "2") (pinfunction "2_2") (pintype "passive"))
      (node (ref "U$12") (pin "P$10") (pinfunction "10_P$10") (pintype "passive"))
    )
    (net (code "29") (name "/SWD") (class "Default")
      (node (ref "IC2") (pin "34") (pinfunction "PA13_34") (pintype "bidirectional"))
      (node (ref "R64") (pin "2") (pinfunction "2_2") (pintype "passive"))
      (node (ref "U$12") (pin "P$8") (pinfunction "8_P$8") (pintype "passive"))
    )
    (net (code "30") (name "/TIME") (class "Default")
      (node (ref "IC2") (pin "42") (pinfunction "PB6_42") (pintype "bidirectional"))
      (node (ref "JP1") (pin "15") (pinfunction "15_15") (pintype "passive"))
    )
    (net (code "31") (name "/TX-S") (class "Default")
      (node (ref "IC2") (pin "30") (pinfunction "PA9_30") (pintype "bidirectional"))
      (node (ref "U$12") (pin "P$6") (pinfunction "6_P$6") (pintype "passive"))
    )
    (net (code "32") (name "/Y") (class "Default")
      (node (ref "INVERT") (pin "P$4") (pinfunction "Y_P$4") (pintype "bidirectional"))
      (node (ref "R57") (pin "1") (pinfunction "1_1") (pintype "passive"))
      (node (ref "U$59") (pin "18") (pinfunction "RUN_18") (pintype "bidirectional"))
    )
    (net (code "33") (name "Net-(3,3µH-Pad1)") (class "Default")
      (node (ref "3,3µH") (pin "1") (pinfunction "1_1") (pintype "bidirectional"))
      (node (ref "C41") (pin "1") (pinfunction "1_1") (pintype "passive"))
      (node (ref "U$59") (pin "5") (pinfunction "SW2_5") (pintype "bidirectional"))
      (node (ref "U$59") (pin "8") (pinfunction "SW2_8") (pintype "bidirectional"))
    )
    (net (code "34") (name "Net-(3,3µH-Pad2)") (class "Default")
      (node (ref "3,3µH") (pin "2") (pinfunction "2_2") (pintype "bidirectional"))
      (node (ref "C40") (pin "1") (pinfunction "1_1") (pintype "passive"))
      (node (ref "U$59") (pin "21") (pinfunction "SW1_21") (pintype "bidirectional"))
      (node (ref "U$59") (pin "24") (pinfunction "SW1_24") (pintype "bidirectional"))
    )
    (net (code "35") (name "Net-(3,3µH1-Pad1)") (class "Default")
      (node (ref "3,3µH1") (pin "1") (pinfunction "1_1") (pintype "bidirectional"))
      (node (ref "C50") (pin "1") (pinfunction "1_1") (pintype "passive"))
      (node (ref "U$23") (pin "5") (pinfunction "SW2_5") (pintype "bidirectional"))
      (node (ref "U$23") (pin "8") (pinfunction "SW2_8") (pintype "bidirectional"))
    )
    (net (code "36") (name "Net-(3,3µH1-Pad2)") (class "Default")
      (node (ref "3,3µH1") (pin "2") (pinfunction "2_2") (pintype "bidirectional"))
      (node (ref "C49") (pin "1") (pinfunction "1_1") (pintype "passive"))
      (node (ref "U$23") (pin "21") (pinfunction "SW1_21") (pintype "bidirectional"))
      (node (ref "U$23") (pin "24") (pinfunction "SW1_24") (pintype "bidirectional"))
    )
    (net (code "37") (name "Net-(AD5272#2-A)") (class "Default")
      (node (ref "AD5272#2") (pin "2") (pinfunction "A_2") (pintype "bidirectional"))
      (node (ref "R1") (pin "2") (pinfunction "2_2") (pintype "passive"))
      (node (ref "U$23") (pin "12") (pinfunction "FB_12") (pintype "bidirectional"))
    )
    (net (code "38") (name "Net-(AD5272#2-CAP)") (class "Default")
      (node (ref "AD5272#2") (pin "5") (pinfunction "CAP_5") (pintype "bidirectional"))
      (node (ref "C29") (pin "1") (pinfunction "1_1") (pintype "passive"))
    )
    (net (code "39") (name "Net-(AD5272#2-VDD)") (class "Default")
      (node (ref "AD5272#2") (pin "1") (pinfunction "VDD_1") (pintype "bidirectional"))
      (node (ref "C53") (pin "1") (pinfunction "1_1") (pintype "passive"))
      (node (ref "C56") (pin "1") (pinfunction "1_1") (pintype "passive"))
      (node (ref "C57") (pin "1") (pinfunction "1_1") (pintype "passive"))
      (node (ref "LED_G2") (pin "A") (pinfunction "A_A") (pintype "passive"))
      (node (ref "U$23") (pin "11") (pinfunction "SVCC_11") (pintype "bidirectional"))
      (node (ref "U$23") (pin "15") (pinfunction "MPPC_15") (pintype "bidirectional"))
      (node (ref "U$23") (pin "16") (pinfunction "VCC_16") (pintype "bidirectional"))
    )
    (net (code "40") (name "Net-(AD5272#2-VSS)") (class "Default")
      (node (ref "AD5272#2") (pin "3") (pinfunction "W_3") (pintype "bidirectional"))
      (node (ref "AD5272#2") (pin "4") (pinfunction "VSS_4") (pintype "bidirectional"))
      (node (ref "C29") (pin "2") (pinfunction "2_2") (pintype "passive"))
      (node (ref "R3") (pin "1") (pinfunction "1_1") (pintype "passive"))
    )
    (net (code "41") (name "Net-(C44-Pad1)") (class "Default")
      (node (ref "C44") (pin "1") (pinfunction "1_1") (pintype "passive"))
      (node (ref "R69") (pin "2") (pinfunction "2_2") (pintype "passive"))
    )
    (net (code "42") (name "Net-(C46-Pad1)") (class "Default")
      (node (ref "C46") (pin "1") (pinfunction "1_1") (pintype "passive"))
      (node (ref "R66") (pin "1") (pinfunction "1_1") (pintype "passive"))
    )
    (net (code "43") (name "Net-(C52-Pad1)") (class "Default")
      (node (ref "C52") (pin "1") (pinfunction "1_1") (pintype "passive"))
      (node (ref "R30") (pin "2") (pinfunction "2_2") (pintype "passive"))
    )
    (net (code "44") (name "Net-(IC2-OSC_IN)") (class "Default")
      (node (ref "C1") (pin "1") (pinfunction "1_1") (pintype "passive"))
      (node (ref "IC2") (pin "5") (pinfunction "OSC_IN_5") (pintype "bidirectional"))
    )
    (net (code "45") (name "Net-(IC2-PB5)") (class "Default")
      (node (ref "IC2") (pin "41") (pinfunction "PB5_41") (pintype "bidirectional"))
      (node (ref "R81") (pin "1") (pinfunction "1_1") (pintype "passive"))
    )
    (net (code "46") (name "Net-(INA219#1-IN+)") (class "Default")
      (node (ref "C9") (pin "1") (pinfunction "1_1") (pintype "passive"))
      (node (ref "INA219#1") (pin "1") (pinfunction "IN+_1") (pintype "bidirectional"))
      (node (ref "R73") (pin "2") (pinfunction "2_2") (pintype "passive"))
    )
    (net (code "47") (name "Net-(INA219#1-IN-)") (class "Default")
      (node (ref "C9") (pin "2") (pinfunction "2_2") (pintype "passive"))
      (node (ref "INA219#1") (pin "2") (pinfunction "IN-_2") (pintype "bidirectional"))
      (node (ref "R74") (pin "2") (pinfunction "2_2") (pintype "passive"))
    )
    (net (code "48") (name "Net-(INA219#2-IN+)") (class "Default")
      (node (ref "C10") (pin "1") (pinfunction "1_1") (pintype "passive"))
      (node (ref "INA219#2") (pin "1") (pinfunction "IN+_1") (pintype "bidirectional"))
      (node (ref "R76") (pin "2") (pinfunction "2_2") (pintype "passive"))
    )
    (net (code "49") (name "Net-(INA219#2-IN-)") (class "Default")
      (node (ref "C10") (pin "2") (pinfunction "2_2") (pintype "passive"))
      (node (ref "INA219#2") (pin "2") (pinfunction "IN-_2") (pintype "bidirectional"))
      (node (ref "R77") (pin "2") (pinfunction "2_2") (pintype "passive"))
    )
    (net (code "50") (name "Net-(LED_G1-PadC)") (class "Default")
      (node (ref "LED_G1") (pin "C") (pinfunction "C_C") (pintype "passive"))
      (node (ref "R100") (pin "2") (pinfunction "2_2") (pintype "passive"))
    )
    (net (code "51") (name "Net-(LED_G2-PadC)") (class "Default")
      (node (ref "LED_G2") (pin "C") (pinfunction "C_C") (pintype "passive"))
      (node (ref "R33") (pin "2") (pinfunction "2_2") (pintype "passive"))
    )
    (net (code "52") (name "Net-(LED_R1-PadA)") (class "Default")
      (node (ref "LED_R1") (pin "A") (pinfunction "A_A") (pintype "passive"))
      (node (ref "R32") (pin "2") (pinfunction "2_2") (pintype "passive"))
    )
    (net (code "53") (name "Net-(LED_R2-PadA)") (class "Default")
      (node (ref "LED_R2") (pin "A") (pinfunction "A_A") (pintype "passive"))
      (node (ref "R57") (pin "2") (pinfunction "2_2") (pintype "passive"))
    )
    (net (code "54") (name "Net-(OPA-IN+)") (class "Default")
      (node (ref "OPA") (pin "P$3") (pinfunction "IN+_P$3") (pintype "bidirectional"))
      (node (ref "R4") (pin "2") (pinfunction "2_2") (pintype "passive"))
      (node (ref "R5") (pin "2") (pinfunction "2_2") (pintype "passive"))
      (node (ref "R7") (pin "2") (pinfunction "2_2") (pintype "passive"))
    )
    (net (code "55") (name "Net-(PB5-PadC)") (class "Default")
      (node (ref "PB5") (pin "C") (pinfunction "C_C") (pintype "passive"))
      (node (ref "R81") (pin "2") (pinfunction "2_2") (pintype "passive"))
    )
    (net (code "56") (name "Net-(PWR-PadC)") (class "Default")
      (node (ref "PWR") (pin "C") (pinfunction "C_C") (pintype "passive"))
      (node (ref "R82") (pin "2") (pinfunction "2_2") (pintype "passive"))
    )
    (net (code "57") (name "Net-(TCXO-OUTPUT)") (class "Default")
      (node (ref "C1") (pin "2") (pinfunction "2_2") (pintype "passive"))
      (node (ref "TCXO") (pin "P$3") (pinfunction "OUTPUT_P$3") (pintype "bidirectional"))
    )
    (net (code "58") (name "Net-(U$23-BST1)") (class "Default")
      (node (ref "C49") (pin "2") (pinfunction "2_2") (pintype "passive"))
      (node (ref "U$23") (pin "26") (pinfunction "BST1_26") (pintype "bidirectional"))
    )
    (net (code "59") (name "Net-(U$23-BST2)") (class "Default")
      (node (ref "C50") (pin "2") (pinfunction "2_2") (pintype "passive"))
      (node (ref "U$23") (pin "3") (pinfunction "BST2_3") (pintype "bidirectional"))
    )
    (net (code "60") (name "Net-(U$23-RT)") (class "Default")
      (node (ref "R28") (pin "2") (pinfunction "2_2") (pintype "passive"))
      (node (ref "U$23") (pin "17") (pinfunction "RT_17") (pintype "bidirectional"))
    )
    (net (code "61") (name "Net-(U$23-VC)") (class "Default")
      (node (ref "R30") (pin "1") (pinfunction "1_1") (pintype "passive"))
      (node (ref "U$23") (pin "13") (pinfunction "VC_13") (pintype "bidirectional"))
    )
    (net (code "62") (name "Net-(U$59-BST1)") (class "Default")
      (node (ref "C40") (pin "2") (pinfunction "2_2") (pintype "passive"))
      (node (ref "U$59") (pin "26") (pinfunction "BST1_26") (pintype "bidirectional"))
    )
    (net (code "63") (name "Net-(U$59-BST2)") (class "Default")
      (node (ref "C41") (pin "2") (pinfunction "2_2") (pintype "passive"))
      (node (ref "U$59") (pin "3") (pinfunction "BST2_3") (pintype "bidirectional"))
    )
    (net (code "64") (name "Net-(U$59-FB)") (class "Default")
      (node (ref "U$59") (pin "12") (pinfunction "FB_12") (pintype "bidirectional"))
      (node (ref "VR-FB") (pin "2") (pinfunction "WIPER_2") (pintype "passive"))
    )
    (net (code "65") (name "Net-(U$59-MPPC)") (class "Default")
      (node (ref "R65") (pin "1") (pinfunction "1_1") (pintype "passive"))
      (node (ref "R66") (pin "2") (pinfunction "2_2") (pintype "passive"))
      (node (ref "R67") (pin "2") (pinfunction "2_2") (pintype "passive"))
      (node (ref "U$59") (pin "15") (pinfunction "MPPC_15") (pintype "bidirectional"))
    )
    (net (code "66") (name "Net-(U$59-RT)") (class "Default")
      (node (ref "R68") (pin "2") (pinfunction "2_2") (pintype "passive"))
      (node (ref "U$59") (pin "17") (pinfunction "RT_17") (pintype "bidirectional"))
    )
    (net (code "67") (name "Net-(U$59-SVCC)") (class "Default")
      (node (ref "C45") (pin "1") (pinfunction "1_1") (pintype "passive"))
      (node (ref "LED_G1") (pin "A") (pinfunction "A_A") (pintype "passive"))
      (node (ref "U$59") (pin "11") (pinfunction "SVCC_11") (pintype "bidirectional"))
      (node (ref "U$59") (pin "16") (pinfunction "VCC_16") (pintype "bidirectional"))
    )
    (net (code "68") (name "Net-(U$59-VC)") (class "Default")
      (node (ref "R69") (pin "1") (pinfunction "1_1") (pintype "passive"))
      (node (ref "U$59") (pin "13") (pinfunction "VC_13") (pintype "bidirectional"))
    )
    (net (code "69") (name "unconnected-(IC2-OSC_OUT-Pad6)") (class "Default")
      (node (ref "IC2") (pin "6") (pinfunction "OSC_OUT_6") (pintype "bidirectional"))
    )
    (net (code "70") (name "unconnected-(IC2-PA0-WKUP-Pad10)") (class "Default")
      (node (ref "IC2") (pin "10") (pinfunction "PA0-WKUP_10") (pintype "bidirectional"))
    )
    (net (code "71") (name "unconnected-(IC2-PA8-Pad29)") (class "Default")
      (node (ref "IC2") (pin "29") (pinfunction "PA8_29") (pintype "bidirectional"))
    )
    (net (code "72") (name "unconnected-(IC2-PA11-Pad32)") (class "Default")
      (node (ref "IC2") (pin "32") (pinfunction "PA11_32") (pintype "bidirectional"))
    )
    (net (code "73") (name "unconnected-(IC2-PA12-Pad33)") (class "Default")
      (node (ref "IC2") (pin "33") (pinfunction "PA12_33") (pintype "bidirectional"))
    )
    (net (code "74") (name "unconnected-(IC2-PA15-Pad38)") (class "Default")
      (node (ref "IC2") (pin "38") (pinfunction "PA15_38") (pintype "bidirectional"))
    )
    (net (code "75") (name "unconnected-(IC2-PB3-Pad39)") (class "Default")
      (node (ref "IC2") (pin "39") (pinfunction "PB3_39") (pintype "bidirectional"))
    )
    (net (code "76") (name "unconnected-(IC2-PB4-Pad40)") (class "Default")
      (node (ref "IC2") (pin "40") (pinfunction "PB4_40") (pintype "bidirectional"))
    )
    (net (code "77") (name "unconnected-(IC2-PB7-Pad43)") (class "Default")
      (node (ref "IC2") (pin "43") (pinfunction "PB7_43") (pintype "bidirectional"))
    )
    (net (code "78") (name "unconnected-(IC2-PB12-Pad25)") (class "Default")
      (node (ref "IC2") (pin "25") (pinfunction "PB12_25") (pintype "bidirectional"))
    )
    (net (code "79") (name "unconnected-(IC2-PB13-Pad26)") (class "Default")
      (node (ref "IC2") (pin "26") (pinfunction "PB13_26") (pintype "bidirectional"))
    )
    (net (code "80") (name "unconnected-(IC2-PB14-Pad27)") (class "Default")
      (node (ref "IC2") (pin "27") (pinfunction "PB14_27") (pintype "bidirectional"))
    )
    (net (code "81") (name "unconnected-(IC2-PC13-Pad2)") (class "Default")
      (node (ref "IC2") (pin "2") (pinfunction "PC13_2") (pintype "bidirectional"))
    )
    (net (code "82") (name "unconnected-(IC2-PC14-Pad3)") (class "Default")
      (node (ref "IC2") (pin "3") (pinfunction "PC14_3") (pintype "bidirectional"))
    )
    (net (code "83") (name "unconnected-(IC2-PC15-Pad4)") (class "Default")
      (node (ref "IC2") (pin "4") (pinfunction "PC15_4") (pintype "bidirectional"))
    )
    (net (code "84") (name "unconnected-(INVERT-NC-PadP$1)") (class "Default")
      (node (ref "INVERT") (pin "P$1") (pinfunction "NC_P$1") (pintype "bidirectional"))
    )
    (net (code "85") (name "unconnected-(JP1-Pad9)") (class "Default")
      (node (ref "JP1") (pin "9") (pinfunction "9_9") (pintype "passive"))
    )
    (net (code "86") (name "unconnected-(JP1-Pad10)") (class "Default")
      (node (ref "JP1") (pin "10") (pinfunction "10_10") (pintype "passive"))
    )
    (net (code "87") (name "unconnected-(U$12-12-PadP$12)") (class "Default")
      (node (ref "U$12") (pin "P$12") (pinfunction "12_P$12") (pintype "passive"))
    )
    (net (code "88") (name "unconnected-(U$12-13-PadP$13)") (class "Default")
      (node (ref "U$12") (pin "P$13") (pinfunction "13_P$13") (pintype "passive"))
    )
    (net (code "89") (name "unconnected-(U$12-14-PadP$14)") (class "Default")
      (node (ref "U$12") (pin "P$14") (pinfunction "14_P$14") (pintype "passive"))
    )
    (net (code "90") (name "unconnected-(U$12-15-PadP$15)") (class "Default")
      (node (ref "U$12") (pin "P$15") (pinfunction "15_P$15") (pintype "passive"))
    )
  )
)
